# Pushbuttons.net
KiCad netlist of a schematic drawn in Altium Designer
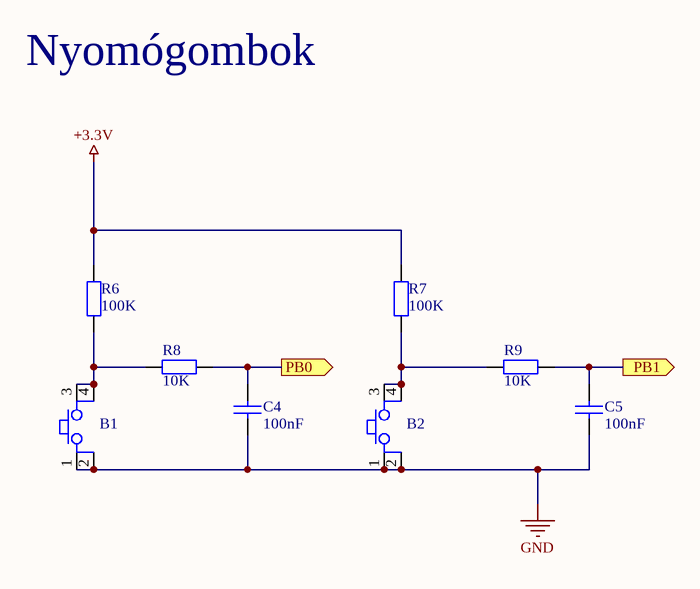
[diagram p0: Pushbuttons.SchDoc]

(export (version "E")
  (design (tool "Eeschema 10.0.6"))
  (components
    (comp (ref "B1")
      (value "Button")
      (footprint "FP_BTN_SMD")
      (description "Push button")
      (libsource (lib "hallglib") (part "Button 4P"))
    )
    (comp (ref "B2")
      (value "Button")
      (footprint "FP_BTN_SMD")
      (description "Push button")
      (libsource (lib "hallglib") (part "Button 4P"))
    )
    (comp (ref "C4")
      (value "100nF")
      (footprint "FP_1206_CAP_125")
      (description "Capacitor")
      (fields (field (name "TOLERANCE") "10%") (field (name "VOLTAGE") "50V"))
      (libsource (lib "hallglib") (part "CAP"))
    )
    (comp (ref "C5")
      (value "100nF")
      (footprint "FP_1206_CAP_125")
      (description "Capacitor")
      (fields (field (name "TOLERANCE") "10%") (field (name "VOLTAGE") "50V"))
      (libsource (lib "hallglib") (part "CAP"))
    )
    (comp (ref "R6")
      (value "100K")
      (footprint "FP_1206_RES")
      (description "Resistor")
      (fields (field (name "TOLERANCE") "5%") (field (name "POWER") "0.25W"))
      (libsource (lib "hallglib") (part "RES"))
    )
    (comp (ref "R7")
      (value "100K")
      (footprint "FP_1206_RES")
      (description "Resistor")
      (fields (field (name "TOLERANCE") "5%") (field (name "POWER") "0.25W"))
      (libsource (lib "hallglib") (part "RES"))
    )
    (comp (ref "R8")
      (value "10K")
      (footprint "FP_1206_RES")
      (description "Resistor")
      (fields (field (name "TOLERANCE") "5%") (field (name "POWER") "0.25W"))
      (libsource (lib "") (part "RES_1"))
    )
    (comp (ref "R9")
      (value "10K")
      (footprint "FP_1206_RES")
      (description "Resistor")
      (fields (field (name "TOLERANCE") "5%") (field (name "POWER") "0.25W"))
      (libsource (lib "") (part "RES_1"))
    )
  )
  (nets
    (net (code "1") (name "+3.3V") (class "Default")
      (node (ref "R6") (pin "2") (pinfunction "2_2") (pintype "passive"))
      (node (ref "R7") (pin "2") (pinfunction "2_2") (pintype "passive"))
    )
    (net (code "2") (name "/PB0") (class "Default")
      (node (ref "C4") (pin "2") (pinfunction "2_2") (pintype "passive"))
      (node (ref "R8") (pin "2") (pinfunction "2_2") (pintype "passive"))
    )
    (net (code "3") (name "/PB1") (class "Default")
      (node (ref "C5") (pin "2") (pinfunction "2_2") (pintype "passive"))
      (node (ref "R9") (pin "2") (pinfunction "2_2") (pintype "passive"))
    )
    (net (code "4") (name "GND") (class "Default")
      (node (ref "B1") (pin "1") (pinfunction "1_1") (pintype "passive"))
      (node (ref "B1") (pin "2") (pinfunction "2_2") (pintype "passive"))
      (node (ref "B2") (pin "1") (pinfunction "1_1") (pintype "passive"))
      (node (ref "B2") (pin "2") (pinfunction "2_2") (pintype "passive"))
      (node (ref "C4") (pin "1") (pinfunction "1_1") (pintype "passive"))
      (node (ref "C5") (pin "1") (pinfunction "1_1") (pintype "passive"))
    )
    (net (code "5") (name "Net-(B1-Pad3)") (class "Default")
      (node (ref "B1") (pin "3") (pinfunction "3_3") (pintype "passive"))
      (node (ref "B1") (pin "4") (pinfunction "4_4") (pintype "passive"))
      (node (ref "R6") (pin "1") (pinfunction "1_1") (pintype "passive"))
      (node (ref "R8") (pin "1") (pinfunction "1_1") (pintype "passive"))
    )
    (net (code "6") (name "Net-(B2-Pad3)") (class "Default")
      (node (ref "B2") (pin "3") (pinfunction "3_3") (pintype "passive"))
      (node (ref "B2") (pin "4") (pinfunction "4_4") (pintype "passive"))
      (node (ref "R7") (pin "1") (pinfunction "1_1") (pintype "passive"))
      (node (ref "R9") (pin "1") (pinfunction "1_1") (pintype "passive"))
    )
  )
)
